# light_detector.net
KiCad netlist of a schematic drawn in EAGLE
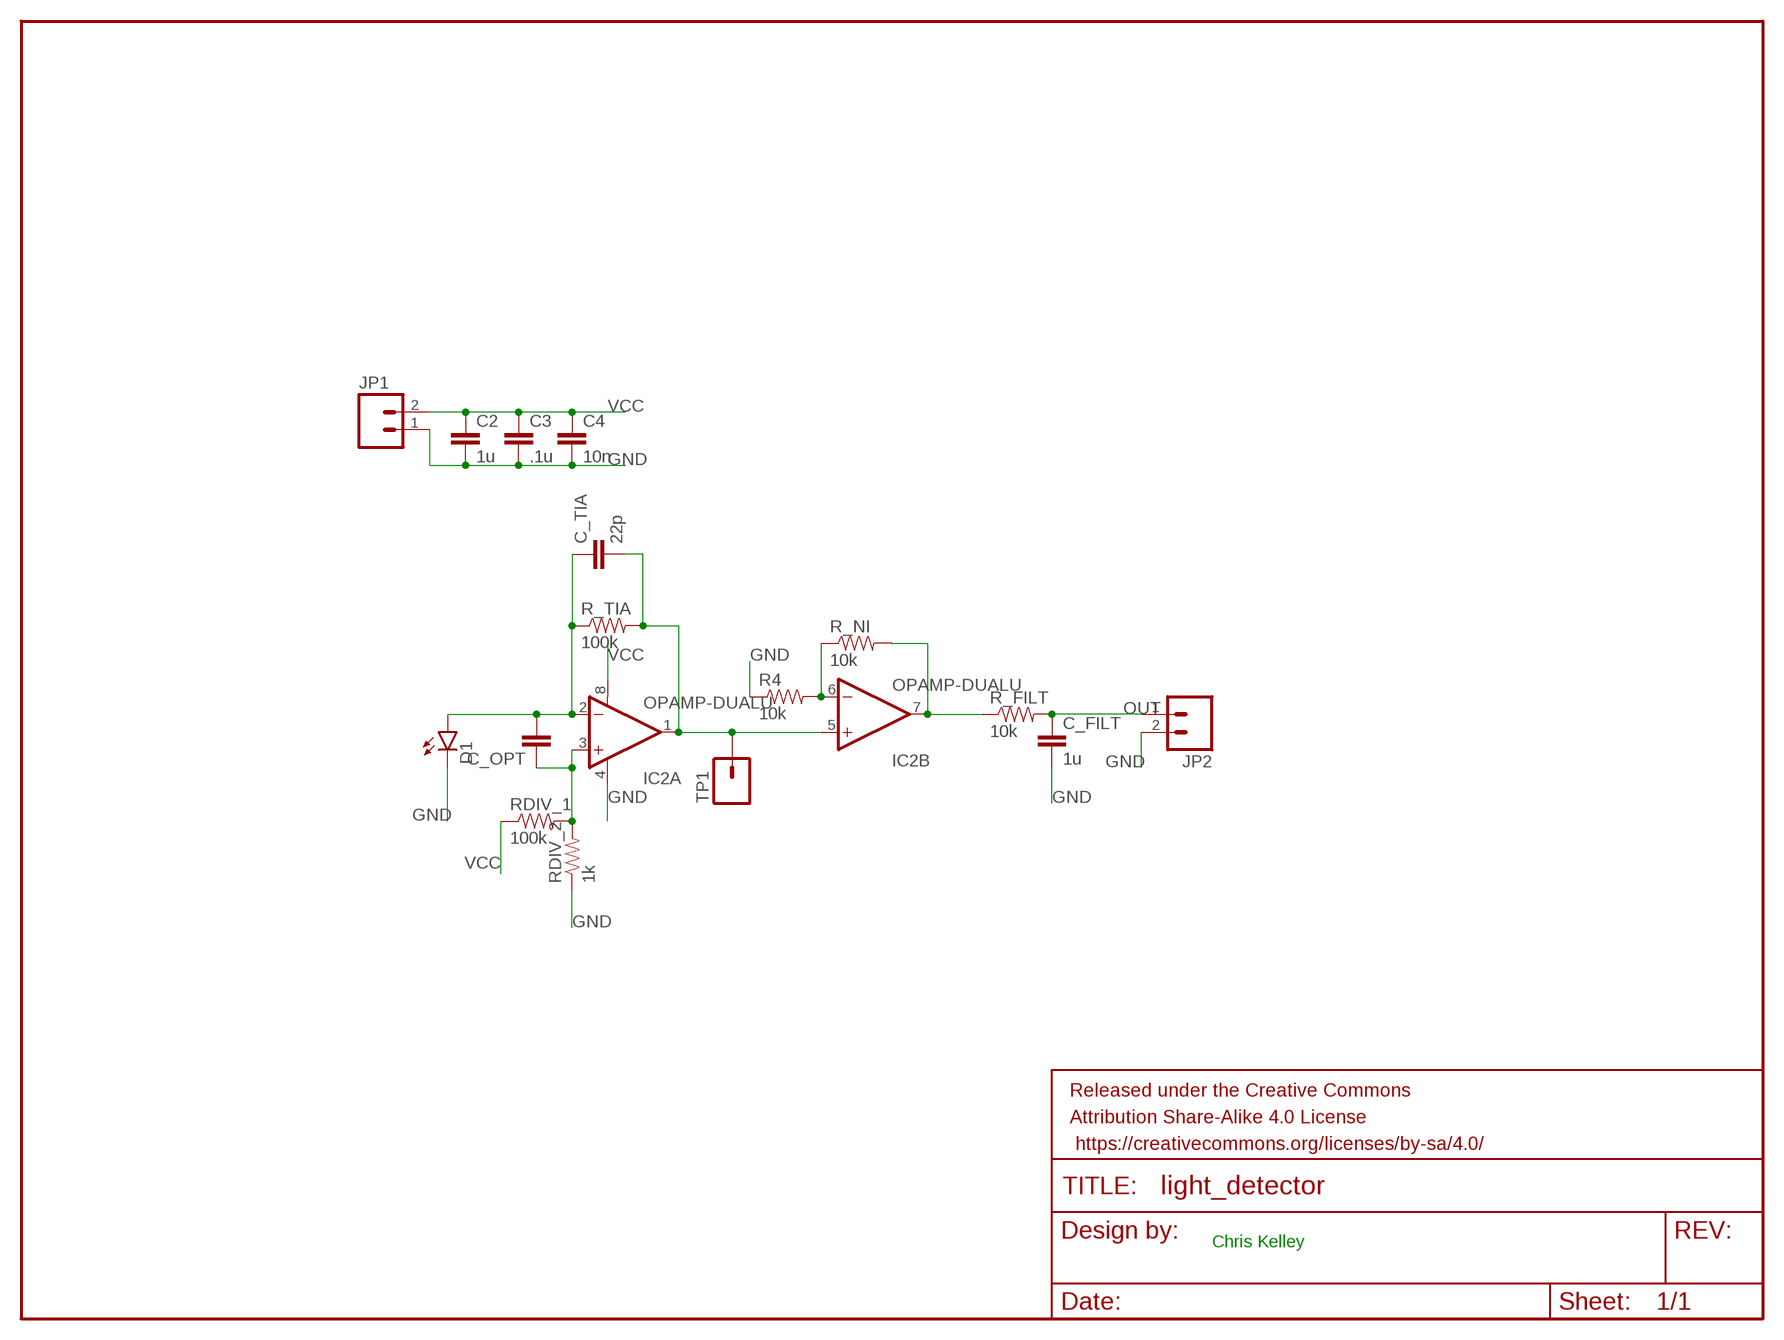
[diagram p0: schematic, sheet 1]

(export (version "E")
  (design (tool "Eeschema 10.0.6"))
  (components
    (comp (ref "C2")
      (value "1u")
      (footprint "eagle-import:0805")
      (libsource (lib "eagle-import") (part "CAP0805"))
    )
    (comp (ref "C3")
      (value ".1u")
      (footprint "eagle-import:0805")
      (libsource (lib "eagle-import") (part "CAP0805"))
    )
    (comp (ref "C4")
      (value "10n")
      (footprint "eagle-import:0805")
      (libsource (lib "eagle-import") (part "CAP0805"))
    )
    (comp (ref "C_FILT")
      (value "1u")
      (footprint "eagle-import:0805")
      (libsource (lib "eagle-import") (part "CAP0805"))
    )
    (comp (ref "C_OPT")
      (value "CAP0805")
      (footprint "eagle-import:0805")
      (libsource (lib "eagle-import") (part "CAP0805"))
    )
    (comp (ref "C_TIA")
      (value "22p")
      (footprint "eagle-import:0805")
      (libsource (lib "eagle-import") (part "CAP0805"))
    )
    (comp (ref "D1")
      (value "LED5MM")
      (footprint "eagle-import:LED5MM")
      (libsource (lib "eagle-import") (part "LED5MM"))
    )
    (comp (ref "FRAME1")
      (value "FRAME-LETTER")
      (footprint "eagle-import:CREATIVE_COMMONS")
      (libsource (lib "eagle-import") (part "FRAME-LETTER"))
    )
    (comp (ref "IC2")
      (value "OPAMP-DUALU")
      (footprint "eagle-import:SO08")
      (libsource (lib "eagle-import") (part "OPAMP-DUALU"))
    )
    (comp (ref "JP1")
      (value "M02PTH")
      (footprint "eagle-import:1X02")
      (libsource (lib "eagle-import") (part "M02PTH"))
    )
    (comp (ref "JP2")
      (value "M02PTH")
      (footprint "eagle-import:1X02")
      (libsource (lib "eagle-import") (part "M02PTH"))
    )
    (comp (ref "R4")
      (value "10k")
      (footprint "eagle-import:0603-RES")
      (libsource (lib "eagle-import") (part "RESISTOR0603-RES"))
    )
    (comp (ref "RDIV_1")
      (value "100k")
      (footprint "eagle-import:0603-RES")
      (libsource (lib "eagle-import") (part "RESISTOR0603-RES"))
    )
    (comp (ref "RDIV_2")
      (value "1k")
      (footprint "eagle-import:0603-RES")
      (libsource (lib "eagle-import") (part "RESISTOR0603-RES"))
    )
    (comp (ref "R_FILT")
      (value "10k")
      (footprint "eagle-import:0603-RES")
      (libsource (lib "eagle-import") (part "RESISTOR0603-RES"))
    )
    (comp (ref "R_NI")
      (value "10k")
      (footprint "eagle-import:0603-RES")
      (libsource (lib "eagle-import") (part "RESISTOR0603-RES"))
    )
    (comp (ref "R_TIA")
      (value "100k")
      (footprint "eagle-import:0603-RES")
      (libsource (lib "eagle-import") (part "RESISTOR0603-RES"))
    )
    (comp (ref "TP1")
      (value "M01PTH")
      (footprint "eagle-import:1X01")
      (libsource (lib "eagle-import") (part "M01PTH"))
    )
  )
  (nets
    (net (code "1") (name "/GND") (class "Default")
      (node (ref "C2") (pin "2") (pinfunction "2_2") (pintype "passive"))
      (node (ref "C3") (pin "2") (pinfunction "2_2") (pintype "passive"))
      (node (ref "C4") (pin "2") (pinfunction "2_2") (pintype "passive"))
      (node (ref "C_FILT") (pin "2") (pinfunction "2_2") (pintype "passive"))
      (node (ref "D1") (pin "K") (pinfunction "C_K") (pintype "passive"))
      (node (ref "IC2") (pin "4") (pinfunction "V-_4") (pintype "power_in"))
      (node (ref "JP1") (pin "1") (pinfunction "1_1") (pintype "passive"))
      (node (ref "JP2") (pin "2") (pinfunction "2_2") (pintype "passive"))
      (node (ref "R4") (pin "1") (pinfunction "1_1") (pintype "passive"))
      (node (ref "RDIV_2") (pin "1") (pinfunction "1_1") (pintype "passive"))
    )
    (net (code "2") (name "/OUT") (class "Default")
      (node (ref "C_FILT") (pin "1") (pinfunction "1_1") (pintype "passive"))
      (node (ref "JP2") (pin "1") (pinfunction "1_1") (pintype "passive"))
      (node (ref "R_FILT") (pin "2") (pinfunction "2_2") (pintype "passive"))
    )
    (net (code "3") (name "/VCC") (class "Default")
      (node (ref "C2") (pin "1") (pinfunction "1_1") (pintype "passive"))
      (node (ref "C3") (pin "1") (pinfunction "1_1") (pintype "passive"))
      (node (ref "C4") (pin "1") (pinfunction "1_1") (pintype "passive"))
      (node (ref "IC2") (pin "8") (pinfunction "V+_8") (pintype "power_in"))
      (node (ref "JP1") (pin "2") (pinfunction "2_2") (pintype "passive"))
      (node (ref "RDIV_1") (pin "1") (pinfunction "1_1") (pintype "passive"))
    )
    (net (code "4") (name "Net-(IC2A-+IN)") (class "Default")
      (node (ref "C_OPT") (pin "1") (pinfunction "1_1") (pintype "passive"))
      (node (ref "IC2") (pin "3") (pinfunction "+IN_3") (pintype "input"))
      (node (ref "RDIV_1") (pin "2") (pinfunction "2_2") (pintype "passive"))
      (node (ref "RDIV_2") (pin "2") (pinfunction "2_2") (pintype "passive"))
    )
    (net (code "5") (name "Net-(IC2A--IN)") (class "Default")
      (node (ref "C_OPT") (pin "2") (pinfunction "2_2") (pintype "passive"))
      (node (ref "C_TIA") (pin "1") (pinfunction "1_1") (pintype "passive"))
      (node (ref "D1") (pin "A") (pinfunction "A_A") (pintype "passive"))
      (node (ref "IC2") (pin "2") (pinfunction "-IN_2") (pintype "input"))
      (node (ref "R_TIA") (pin "1") (pinfunction "1_1") (pintype "passive"))
    )
    (net (code "6") (name "Net-(IC2A-OUT)") (class "Default")
      (node (ref "C_TIA") (pin "2") (pinfunction "2_2") (pintype "passive"))
      (node (ref "IC2") (pin "1") (pinfunction "OUT_1") (pintype "output"))
      (node (ref "IC2") (pin "5") (pinfunction "+IN_5") (pintype "input"))
      (node (ref "R_TIA") (pin "2") (pinfunction "2_2") (pintype "passive"))
      (node (ref "TP1") (pin "1") (pinfunction "1_1") (pintype "passive"))
    )
    (net (code "7") (name "Net-(IC2B--IN)") (class "Default")
      (node (ref "IC2") (pin "6") (pinfunction "-IN_6") (pintype "input"))
      (node (ref "R4") (pin "2") (pinfunction "2_2") (pintype "passive"))
      (node (ref "R_NI") (pin "1") (pinfunction "1_1") (pintype "passive"))
    )
    (net (code "8") (name "Net-(IC2B-OUT)") (class "Default")
      (node (ref "IC2") (pin "7") (pinfunction "OUT_7") (pintype "output"))
      (node (ref "R_FILT") (pin "1") (pinfunction "1_1") (pintype "passive"))
      (node (ref "R_NI") (pin "2") (pinfunction "2_2") (pintype "passive"))
    )
  )
)
